# TOP.net
KiCad netlist of a schematic drawn in Altium Designer
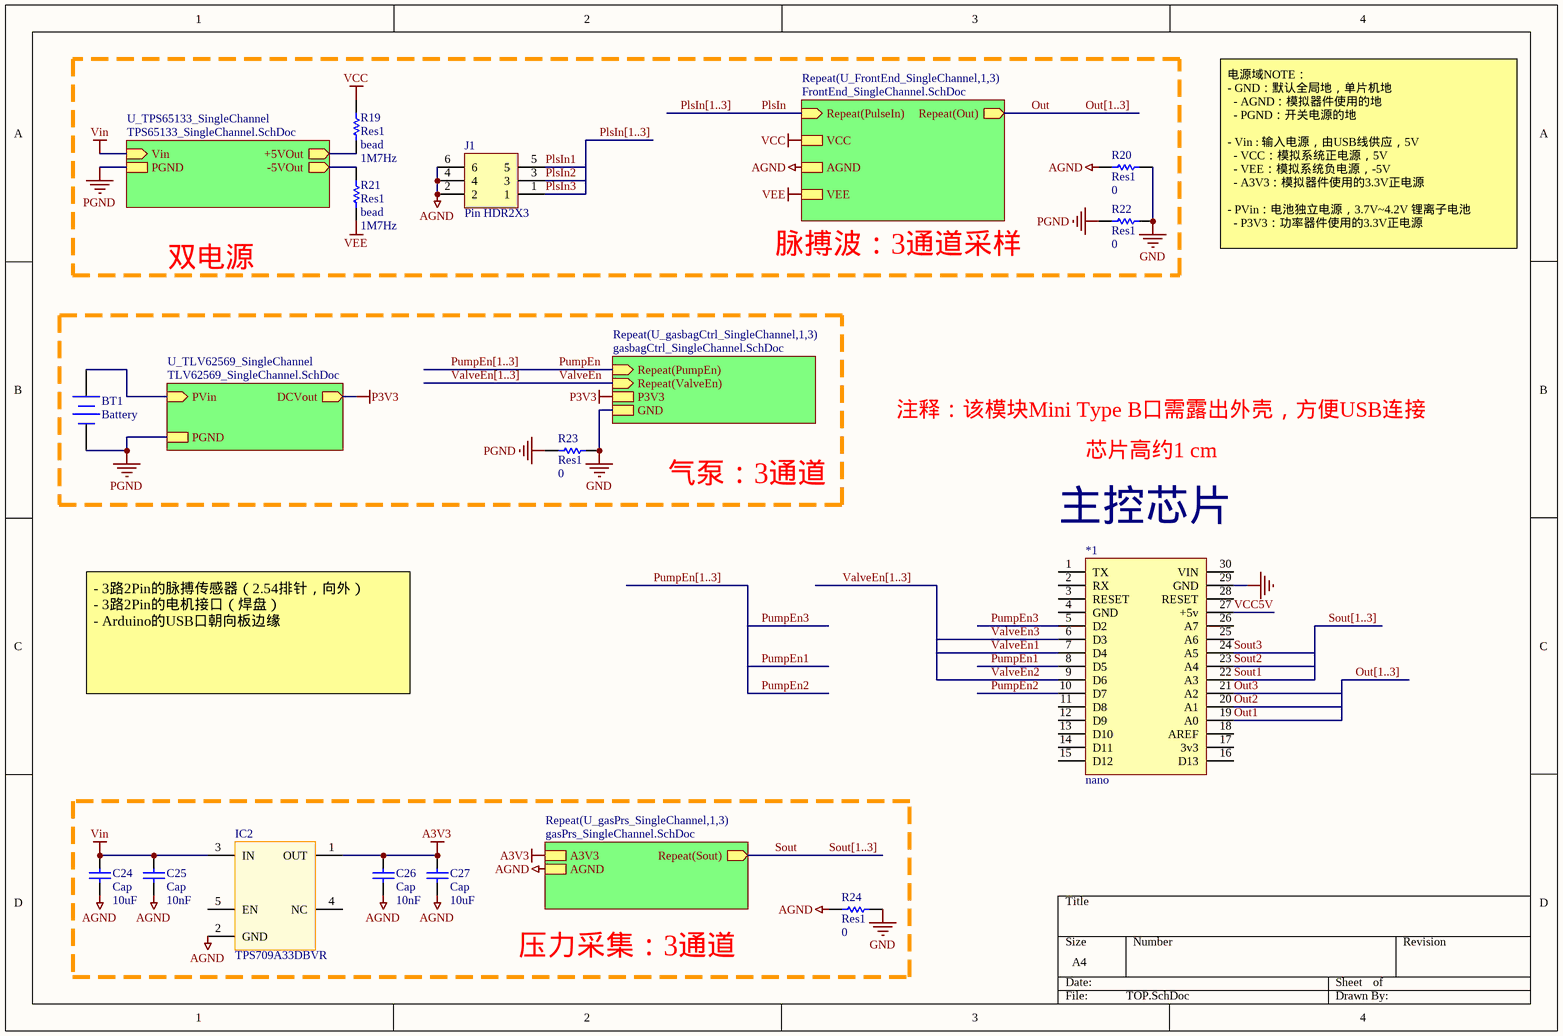
[diagram p0: TOP.SchDoc]

(export (version "E")
  (design (tool "Eeschema 10.0.6"))
  (components
    (comp (ref "*1") (value "nano") (footprint "nano") (libsource (lib "脉诊") (part "nano")))
    (comp (ref "BT1")
      (value "Battery")
      (footprint "BAT-2")
      (description "Multicell Battery")
      (fields (field (name "PUBLISHER") "Altium Limited"))
      (libsource (lib "Miscellaneous Devices") (part "Battery"))
    )
    (comp (ref "C24")
      (value "Cap")
      (footprint "0603C")
      (description "Capacitor")
      (fields (field (name "ALTIUM_VALUE") "10uF") (field (name "PUBLISHER") "Altium Limited"))
      (libsource (lib "Miscellaneous Devices") (part "Cap"))
    )
    (comp (ref "C25")
      (value "Cap")
      (footprint "0603C")
      (description "Capacitor")
      (fields (field (name "ALTIUM_VALUE") "10nF") (field (name "PUBLISHER") "Altium Limited"))
      (libsource (lib "Miscellaneous Devices") (part "Cap"))
    )
    (comp (ref "C26")
      (value "Cap")
      (footprint "0603C")
      (description "Capacitor")
      (fields (field (name "ALTIUM_VALUE") "10nF") (field (name "PUBLISHER") "Altium Limited"))
      (libsource (lib "Miscellaneous Devices") (part "Cap"))
    )
    (comp (ref "C27")
      (value "Cap")
      (footprint "0603C")
      (description "Capacitor")
      (fields (field (name "ALTIUM_VALUE") "10uF") (field (name "PUBLISHER") "Altium Limited"))
      (libsource (lib "Miscellaneous Devices") (part "Cap"))
    )
    (comp (ref "IC2")
      (value "TPS709A33DBVR")
      (footprint "脉诊:SOT95P280X145-5N")
      (description "3.3V 高CMRR LDO")
      (fields (field (name "MOUSER PART NUMBER") "595-TPS709A33DBVR"))
      (libsource (lib "脉诊") (part "TPS709A33DBVR"))
    )
    (comp (ref "J1")
      (value "Pin HDR2X3")
      (footprint "Pin HDR2X3/2.54mm-S")
      (libsource (lib "排针") (part "Pin HDR2X3"))
    )
    (comp (ref "R19")
      (value "Res1")
      (footprint "0603R")
      (description "Resistor")
      (fields
        (field (name "ALTIUM_VALUE") "bead")
        (field (name "FREQUENCY") "1M7Hz")
        (field (name "PUBLISHER") "Altium Limited")
      )
      (libsource (lib "Miscellaneous Devices") (part "Res1"))
    )
    (comp (ref "R20")
      (value "Res1")
      (footprint "0603R")
      (description "Resistor")
      (fields (field (name "ALTIUM_VALUE") "0") (field (name "PUBLISHER") "Altium Limited"))
      (libsource (lib "Miscellaneous Devices") (part "Res1"))
    )
    (comp (ref "R21")
      (value "Res1")
      (footprint "0603R")
      (description "Resistor")
      (fields
        (field (name "ALTIUM_VALUE") "bead")
        (field (name "FREQUENCY") "1M7Hz")
        (field (name "PUBLISHER") "Altium Limited")
      )
      (libsource (lib "Miscellaneous Devices") (part "Res1"))
    )
    (comp (ref "R22")
      (value "Res1")
      (footprint "0603R")
      (description "Resistor")
      (fields (field (name "ALTIUM_VALUE") "0") (field (name "PUBLISHER") "Altium Limited"))
      (libsource (lib "Miscellaneous Devices") (part "Res1"))
    )
    (comp (ref "R23")
      (value "Res1")
      (footprint "0603R")
      (description "Resistor")
      (fields (field (name "ALTIUM_VALUE") "0") (field (name "PUBLISHER") "Altium Limited"))
      (libsource (lib "Miscellaneous Devices") (part "Res1"))
    )
    (comp (ref "R24")
      (value "Res1")
      (footprint "0603R")
      (description "Resistor")
      (fields (field (name "ALTIUM_VALUE") "0") (field (name "PUBLISHER") "Altium Limited"))
      (libsource (lib "Miscellaneous Devices") (part "Res1"))
    )
  )
  (nets
    (net (code "1") (name "/+5VOut") (class "Default")
      (node (ref "R19") (pin "1") (pinfunction "1_1") (pintype "passive"))
    )
    (net (code "2") (name "/-5VOut") (class "Default")
      (node (ref "R21") (pin "2") (pinfunction "2_2") (pintype "passive"))
    )
    (net (code "4") (name "/Out1") (class "Default")
      (node (ref "*1") (pin "19") (pinfunction "A0_19") (pintype "passive"))
    )
    (net (code "5") (name "/Out2") (class "Default")
      (node (ref "*1") (pin "20") (pinfunction "A1_20") (pintype "passive"))
    )
    (net (code "6") (name "/Out3") (class "Default")
      (node (ref "*1") (pin "21") (pinfunction "A2_21") (pintype "passive"))
    )
    (net (code "8") (name "/PVin") (class "Default")
      (node (ref "BT1") (pin "1") (pinfunction "+_1") (pintype "passive"))
    )
    (net (code "10") (name "/PlsIn1") (class "Default")
      (node (ref "J1") (pin "5") (pinfunction "5_5") (pintype "passive"))
    )
    (net (code "11") (name "/PlsIn2") (class "Default")
      (node (ref "J1") (pin "3") (pinfunction "3_3") (pintype "passive"))
    )
    (net (code "12") (name "/PlsIn3") (class "Default")
      (node (ref "J1") (pin "1") (pinfunction "1_1") (pintype "passive"))
    )
    (net (code "15") (name "/PumpEn1") (class "Default")
      (node (ref "*1") (pin "8") (pinfunction "D5_8") (pintype "passive"))
    )
    (net (code "16") (name "/PumpEn2") (class "Default")
      (node (ref "*1") (pin "10") (pinfunction "D7_10") (pintype "passive"))
    )
    (net (code "17") (name "/PumpEn3") (class "Default")
      (node (ref "*1") (pin "5") (pinfunction "D2_5") (pintype "passive"))
    )
    (net (code "20") (name "/Sout1") (class "Default")
      (node (ref "*1") (pin "22") (pinfunction "A3_22") (pintype "passive"))
    )
    (net (code "21") (name "/Sout2") (class "Default")
      (node (ref "*1") (pin "23") (pinfunction "A4_23") (pintype "passive"))
    )
    (net (code "22") (name "/Sout3") (class "Default")
      (node (ref "*1") (pin "24") (pinfunction "A5_24") (pintype "passive"))
    )
    (net (code "24") (name "/VCC5V") (class "Default")
      (node (ref "*1") (pin "27") (pinfunction "+5v_27") (pintype "passive"))
    )
    (net (code "26") (name "/ValveEn1") (class "Default")
      (node (ref "*1") (pin "7") (pinfunction "D4_7") (pintype "passive"))
    )
    (net (code "27") (name "/ValveEn2") (class "Default")
      (node (ref "*1") (pin "9") (pinfunction "D6_9") (pintype "passive"))
    )
    (net (code "28") (name "/ValveEn3") (class "Default")
      (node (ref "*1") (pin "6") (pinfunction "D3_6") (pintype "passive"))
    )
    (net (code "30") (name "A3V3") (class "Default")
      (node (ref "C26") (pin "2") (pinfunction "2_2") (pintype "passive"))
      (node (ref "C27") (pin "2") (pinfunction "2_2") (pintype "passive"))
      (node (ref "IC2") (pin "1") (pinfunction "OUT_1") (pintype "passive"))
    )
    (net (code "31") (name "AGND") (class "Default")
      (node (ref "C24") (pin "1") (pinfunction "1_1") (pintype "passive"))
      (node (ref "C25") (pin "1") (pinfunction "1_1") (pintype "passive"))
      (node (ref "C26") (pin "1") (pinfunction "1_1") (pintype "passive"))
      (node (ref "C27") (pin "1") (pinfunction "1_1") (pintype "passive"))
      (node (ref "IC2") (pin "2") (pinfunction "GND_2") (pintype "passive"))
      (node (ref "J1") (pin "2") (pinfunction "2_2") (pintype "passive"))
      (node (ref "J1") (pin "4") (pinfunction "4_4") (pintype "passive"))
      (node (ref "J1") (pin "6") (pinfunction "6_6") (pintype "passive"))
      (node (ref "R20") (pin "1") (pinfunction "1_1") (pintype "passive"))
      (node (ref "R24") (pin "1") (pinfunction "1_1") (pintype "passive"))
    )
    (net (code "32") (name "GND") (class "Default")
      (node (ref "*1") (pin "29") (pinfunction "GND_29") (pintype "passive"))
      (node (ref "R20") (pin "2") (pinfunction "2_2") (pintype "passive"))
      (node (ref "R22") (pin "2") (pinfunction "2_2") (pintype "passive"))
      (node (ref "R23") (pin "2") (pinfunction "2_2") (pintype "passive"))
      (node (ref "R24") (pin "2") (pinfunction "2_2") (pintype "passive"))
    )
    (net (code "34") (name "PGND") (class "Default")
      (node (ref "BT1") (pin "2") (pinfunction "-_2") (pintype "passive"))
      (node (ref "R22") (pin "1") (pinfunction "1_1") (pintype "passive"))
      (node (ref "R23") (pin "1") (pinfunction "1_1") (pintype "passive"))
    )
    (net (code "35") (name "VCC") (class "Default")
      (node (ref "R19") (pin "2") (pinfunction "2_2") (pintype "passive"))
    )
    (net (code "36") (name "VEE") (class "Default")
      (node (ref "R21") (pin "1") (pinfunction "1_1") (pintype "passive"))
    )
    (net (code "37") (name "Vin") (class "Default")
      (node (ref "C24") (pin "2") (pinfunction "2_2") (pintype "passive"))
      (node (ref "C25") (pin "2") (pinfunction "2_2") (pintype "passive"))
      (node (ref "IC2") (pin "3") (pinfunction "IN_3") (pintype "passive"))
    )
    (net (code "38") (name "unconnected-(*1-3v3-Pad17)") (class "Default")
      (node (ref "*1") (pin "17") (pinfunction "3v3_17") (pintype "passive"))
    )
    (net (code "39") (name "unconnected-(*1-A6-Pad25)") (class "Default")
      (node (ref "*1") (pin "25") (pinfunction "A6_25") (pintype "passive"))
    )
    (net (code "40") (name "unconnected-(*1-A7-Pad26)") (class "Default")
      (node (ref "*1") (pin "26") (pinfunction "A7_26") (pintype "passive"))
    )
    (net (code "41") (name "unconnected-(*1-AREF-Pad18)") (class "Default")
      (node (ref "*1") (pin "18") (pinfunction "AREF_18") (pintype "passive"))
    )
    (net (code "42") (name "unconnected-(*1-D8-Pad11)") (class "Default")
      (node (ref "*1") (pin "11") (pinfunction "D8_11") (pintype "passive"))
    )
    (net (code "43") (name "unconnected-(*1-D9-Pad12)") (class "Default")
      (node (ref "*1") (pin "12") (pinfunction "D9_12") (pintype "passive"))
    )
    (net (code "44") (name "unconnected-(*1-D10-Pad13)") (class "Default")
      (node (ref "*1") (pin "13") (pinfunction "D10_13") (pintype "passive"))
    )
    (net (code "45") (name "unconnected-(*1-D11-Pad14)") (class "Default")
      (node (ref "*1") (pin "14") (pinfunction "D11_14") (pintype "passive"))
    )
    (net (code "46") (name "unconnected-(*1-D12-Pad15)") (class "Default")
      (node (ref "*1") (pin "15") (pinfunction "D12_15") (pintype "passive"))
    )
    (net (code "47") (name "unconnected-(*1-D13-Pad16)") (class "Default")
      (node (ref "*1") (pin "16") (pinfunction "D13_16") (pintype "passive"))
    )
    (net (code "48") (name "unconnected-(*1-GND-Pad4)") (class "Default")
      (node (ref "*1") (pin "4") (pinfunction "GND_4") (pintype "passive"))
    )
    (net (code "49") (name "unconnected-(*1-RESET-Pad3)") (class "Default")
      (node (ref "*1") (pin "3") (pinfunction "RESET_3") (pintype "passive"))
    )
    (net (code "50") (name "unconnected-(*1-RESET-Pad28)") (class "Default")
      (node (ref "*1") (pin "28") (pinfunction "RESET_28") (pintype "passive"))
    )
    (net (code "51") (name "unconnected-(*1-RX-Pad2)") (class "Default")
      (node (ref "*1") (pin "2") (pinfunction "RX_2") (pintype "passive"))
    )
    (net (code "52") (name "unconnected-(*1-TX-Pad1)") (class "Default")
      (node (ref "*1") (pin "1") (pinfunction "TX_1") (pintype "passive"))
    )
    (net (code "53") (name "unconnected-(*1-VIN-Pad30)") (class "Default")
      (node (ref "*1") (pin "30") (pinfunction "VIN_30") (pintype "passive"))
    )
    (net (code "54") (name "unconnected-(IC2-EN-Pad5)") (class "Default")
      (node (ref "IC2") (pin "5") (pinfunction "EN_5") (pintype "passive"))
    )
    (net (code "55") (name "unconnected-(IC2-NC-Pad4)") (class "Default")
      (node (ref "IC2") (pin "4") (pinfunction "NC_4") (pintype "passive"))
    )
  )
)
